# SCH_ProtoDuck_v1_2026-04-04.net
KiCad netlist of a schematic drawn in EasyEDA
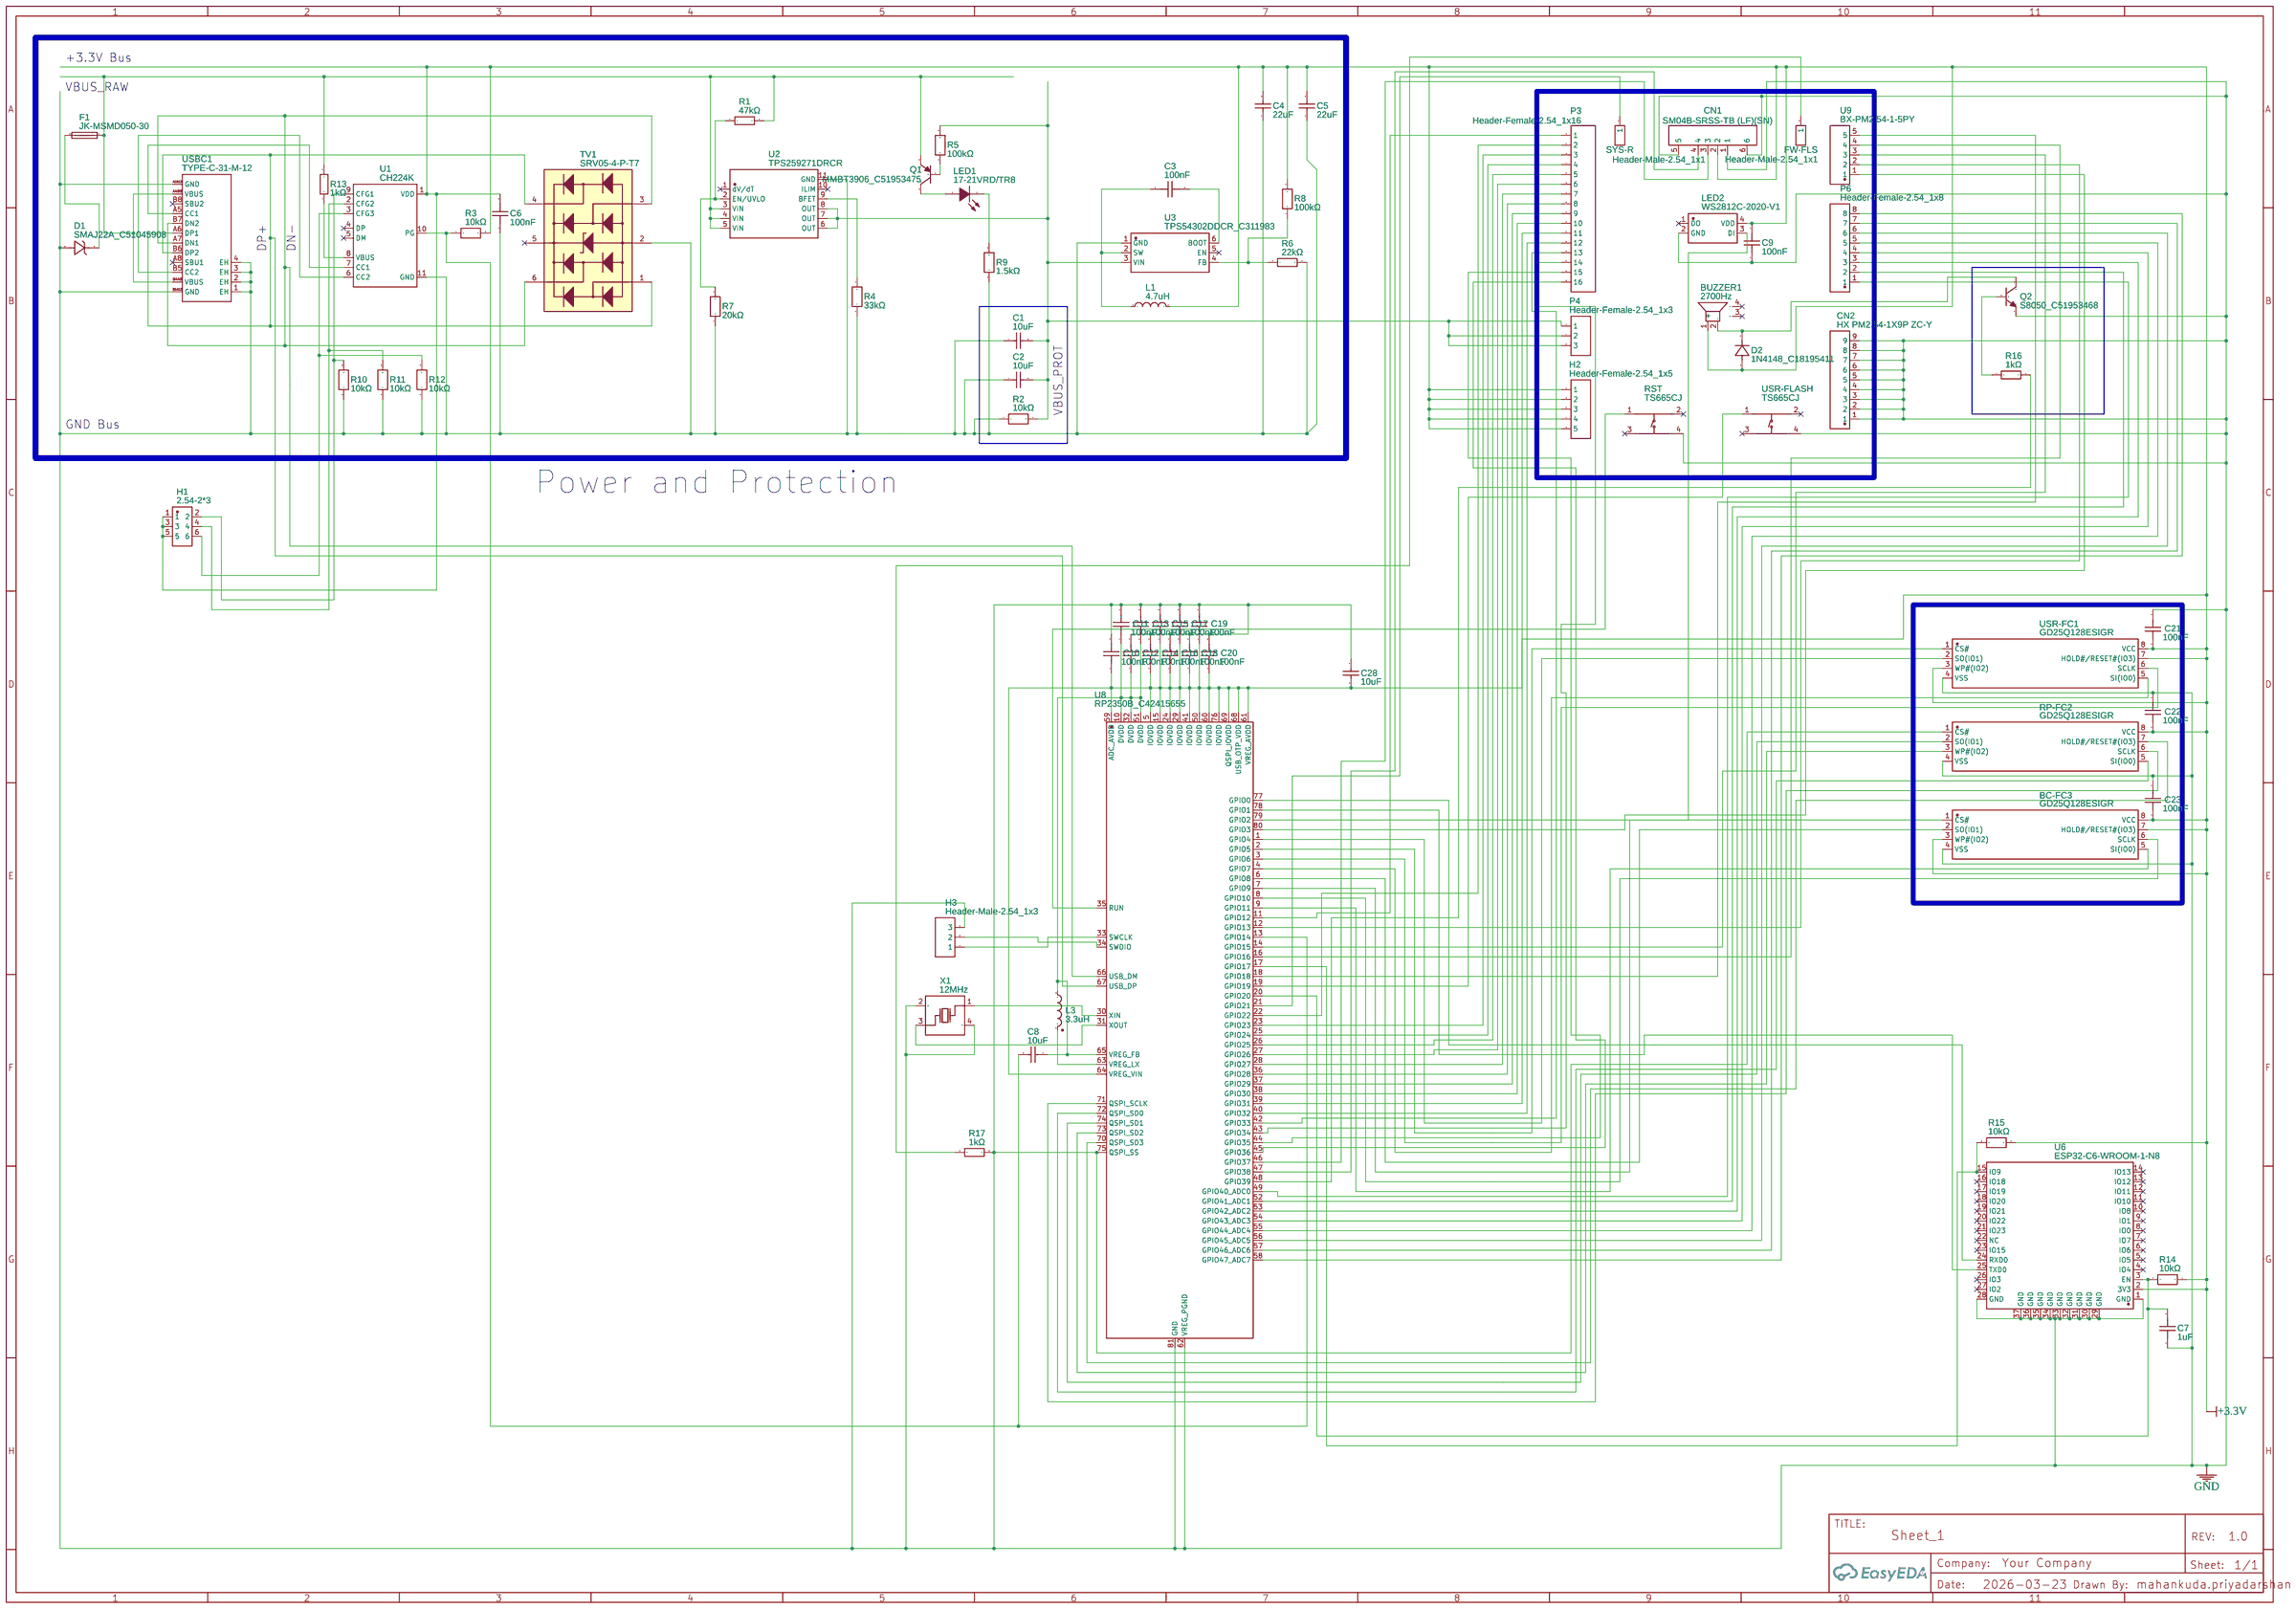
[diagram p0: schematic sheet]

(export (version "E")
  (design (tool "Eeschema 10.0.6"))
  (components
    (comp (ref "BC-FC3")
      (value "GD25Q128ESIGR")
      (fields (field (name "Manufacturer") "GigaDevice(兆易创新)"))
      (libsource (lib "") (part "GD25Q128ESIGR_2"))
    )
    (comp (ref "BUZZER1")
      (value "2700Hz")
      (fields (field (name "Manufacturer Part") "MLT-8540H") (field (name "Manufacturer") "华能"))
      (libsource (lib "") (part "MLT-8540H"))
    )
    (comp (ref "C1")
      (value "10uF")
      (fields
        (field (name "Manufacturer Part") "CL31A106KBHNNNE")
        (field (name "Manufacturer") "SAMSUNG(三星)")
      )
      (libsource (lib "") (part "CL31A106KBHNNNE"))
    )
    (comp (ref "C2")
      (value "10uF")
      (fields
        (field (name "Manufacturer Part") "CL31A106KBHNNNE")
        (field (name "Manufacturer") "SAMSUNG(三星)")
      )
      (libsource (lib "") (part "CL31A106KBHNNNE"))
    )
    (comp (ref "C3")
      (value "100nF")
      (fields
        (field (name "Manufacturer Part") "CC0603KRX7R9BB104")
        (field (name "Manufacturer") "YAGEO(国巨)")
      )
      (libsource (lib "") (part "CC0603KRX7R9BB104"))
    )
    (comp (ref "C4")
      (value "22uF")
      (fields
        (field (name "Manufacturer Part") "CL21A226MOQNNNE")
        (field (name "Manufacturer") "SAMSUNG(三星)")
      )
      (libsource (lib "") (part "CL21A226MOQNNNE"))
    )
    (comp (ref "C5")
      (value "22uF")
      (fields
        (field (name "Manufacturer Part") "CL21A226MOQNNNE")
        (field (name "Manufacturer") "SAMSUNG(三星)")
      )
      (libsource (lib "") (part "CL21A226MOQNNNE"))
    )
    (comp (ref "C6")
      (value "100nF")
      (fields
        (field (name "Manufacturer Part") "CL05B104KB54PNC")
        (field (name "Manufacturer") "SAMSUNG(三星)")
      )
      (libsource (lib "") (part "CL05B104KB54PNC"))
    )
    (comp (ref "C7")
      (value "1uF")
      (fields
        (field (name "Manufacturer Part") "CL10B105KB8NQNC")
        (field (name "Manufacturer") "SAMSUNG(三星)")
      )
      (libsource (lib "") (part "CL10B105KB8NQNC"))
    )
    (comp (ref "C8")
      (value "10uF")
      (fields
        (field (name "Manufacturer Part") "CL31A106KBHNNNE")
        (field (name "Manufacturer") "SAMSUNG(三星)")
      )
      (libsource (lib "") (part "CL31A106KBHNNNE"))
    )
    (comp (ref "C9")
      (value "100nF")
      (fields
        (field (name "Manufacturer Part") "CL05B104KO5NNNC")
        (field (name "Manufacturer") "SAMSUNG(三星)")
      )
      (libsource (lib "") (part "CL05B104KO5NNNC"))
    )
    (comp (ref "C10")
      (value "100nF")
      (fields
        (field (name "Manufacturer Part") "CL05B104KO5NNNC")
        (field (name "Manufacturer") "SAMSUNG(三星)")
      )
      (libsource (lib "") (part "CL05B104KO5NNNC"))
    )
    (comp (ref "C11")
      (value "100nF")
      (fields
        (field (name "Manufacturer Part") "CL05B104KO5NNNC")
        (field (name "Manufacturer") "SAMSUNG(三星)")
      )
      (libsource (lib "") (part "CL05B104KO5NNNC"))
    )
    (comp (ref "C12")
      (value "100nF")
      (fields
        (field (name "Manufacturer Part") "CL05B104KO5NNNC")
        (field (name "Manufacturer") "SAMSUNG(三星)")
      )
      (libsource (lib "") (part "CL05B104KO5NNNC"))
    )
    (comp (ref "C13")
      (value "100nF")
      (fields
        (field (name "Manufacturer Part") "CL05B104KO5NNNC")
        (field (name "Manufacturer") "SAMSUNG(三星)")
      )
      (libsource (lib "") (part "CL05B104KO5NNNC"))
    )
    (comp (ref "C14")
      (value "100nF")
      (fields
        (field (name "Manufacturer Part") "CL05B104KO5NNNC")
        (field (name "Manufacturer") "SAMSUNG(三星)")
      )
      (libsource (lib "") (part "CL05B104KO5NNNC"))
    )
    (comp (ref "C15")
      (value "100nF")
      (fields
        (field (name "Manufacturer Part") "CL05B104KO5NNNC")
        (field (name "Manufacturer") "SAMSUNG(三星)")
      )
      (libsource (lib "") (part "CL05B104KO5NNNC"))
    )
    (comp (ref "C16")
      (value "100nF")
      (fields
        (field (name "Manufacturer Part") "CL05B104KO5NNNC")
        (field (name "Manufacturer") "SAMSUNG(三星)")
      )
      (libsource (lib "") (part "CL05B104KO5NNNC"))
    )
    (comp (ref "C17")
      (value "100nF")
      (fields
        (field (name "Manufacturer Part") "CL05B104KO5NNNC")
        (field (name "Manufacturer") "SAMSUNG(三星)")
      )
      (libsource (lib "") (part "CL05B104KO5NNNC"))
    )
    (comp (ref "C18")
      (value "100nF")
      (fields
        (field (name "Manufacturer Part") "CL05B104KO5NNNC")
        (field (name "Manufacturer") "SAMSUNG(三星)")
      )
      (libsource (lib "") (part "CL05B104KO5NNNC"))
    )
    (comp (ref "C19")
      (value "100nF")
      (fields
        (field (name "Manufacturer Part") "CL05B104KO5NNNC")
        (field (name "Manufacturer") "SAMSUNG(三星)")
      )
      (libsource (lib "") (part "CL05B104KO5NNNC"))
    )
    (comp (ref "C20")
      (value "100nF")
      (fields
        (field (name "Manufacturer Part") "CL05B104KO5NNNC")
        (field (name "Manufacturer") "SAMSUNG(三星)")
      )
      (libsource (lib "") (part "CL05B104KO5NNNC"))
    )
    (comp (ref "C21")
      (value "100nF")
      (fields
        (field (name "Manufacturer Part") "CL05B104KO5NNNC")
        (field (name "Manufacturer") "SAMSUNG(三星)")
      )
      (libsource (lib "") (part "CL05B104KO5NNNC"))
    )
    (comp (ref "C22")
      (value "100nF")
      (fields
        (field (name "Manufacturer Part") "CL05B104KO5NNNC")
        (field (name "Manufacturer") "SAMSUNG(三星)")
      )
      (libsource (lib "") (part "CL05B104KO5NNNC"))
    )
    (comp (ref "C23")
      (value "100nF")
      (fields
        (field (name "Manufacturer Part") "CL05B104KO5NNNC")
        (field (name "Manufacturer") "SAMSUNG(三星)")
      )
      (libsource (lib "") (part "CL05B104KO5NNNC"))
    )
    (comp (ref "C28")
      (value "10uF")
      (fields
        (field (name "Manufacturer Part") "CL05A106MQ5NUNC")
        (field (name "Manufacturer") "SAMSUNG(三星)")
      )
      (libsource (lib "") (part "CL05A106MQ5NUNC"))
    )
    (comp (ref "CN1")
      (value "SM04B-SRSS-TB (LF)(SN)")
      (fields (field (name "Manufacturer Part") "SM04B-SRSS-TB(LF)(SN)") (field (name "Manufacturer") "JST"))
      (libsource (lib "") (part "SM04B-SRSS-TB (LF)(SN)"))
    )
    (comp (ref "CN2")
      (value "HX PM2.54-1X9P ZC-Y")
      (fields
        (field (name "Manufacturer Part") "HX PM2.54-1x9P ZC-Y")
        (field (name "Manufacturer") "hanxia(韩下)")
      )
      (libsource (lib "") (part "HX PM2.54-1X9P ZC-Y"))
    )
    (comp (ref "D1")
      (value "SMAJ22A_C51045908")
      (fields (field (name "Manufacturer Part") "SMAJ22A") (field (name "Manufacturer") "Brightking(君耀电子)"))
      (libsource (lib "") (part "SMAJ22A_C51045908"))
    )
    (comp (ref "D2")
      (value "1N4148_C18195411")
      (fields (field (name "Manufacturer Part") "1N4148") (field (name "Manufacturer") "LJ(朗捷)"))
      (libsource (lib "") (part "1N4148_C18195411"))
    )
    (comp (ref "F1")
      (value "JK-MSMD050-30")
      (fields (field (name "Manufacturer") "JK(金科)"))
      (libsource (lib "") (part "JK-MSMD050-30"))
    )
    (comp (ref "FW-FLS")
      (value "Header-Male-2.54_1x1")
      (fields (field (name "Manufacturer Part") "2.54-1*1P针") (field (name "Manufacturer") "BOOMELE(博穆精密)"))
      (libsource (lib "") (part "Header-Male-2.54_1x1_1"))
    )
    (comp (ref "H1")
      (value "2.54-2*3")
      (fields (field (name "Manufacturer") "ZHOURI(洲日)"))
      (libsource (lib "") (part "2.54-2*3"))
    )
    (comp (ref "H2")
      (value "Header-Female-2.54_1x5")
      (fields (field (name "Manufacturer Part") "2.54-1*5P母") (field (name "Manufacturer") "BOOMELE(博穆精密)"))
      (libsource (lib "") (part "Header-Female-2.54_1x5"))
    )
    (comp (ref "H3")
      (value "Header-Male-2.54_1x3")
      (fields (field (name "Manufacturer Part") "2.54-1*3P针") (field (name "Manufacturer") "BOOMELE(博穆精密)"))
      (libsource (lib "") (part "Header-Male-2.54_1x3"))
    )
    (comp (ref "L1")
      (value "4.7uH")
      (fields
        (field (name "Manufacturer Part") "CKCS6045-4.7uH/M")
        (field (name "Manufacturer") "CENKER(岑科)")
      )
      (libsource (lib "") (part "CKCS6045-4.7UH/M"))
    )
    (comp (ref "L3")
      (value "3.3uH")
      (fields
        (field (name "Manufacturer Part") "AOTA-B201610S3R3-101-T")
        (field (name "Manufacturer") "ABRACON")
      )
      (libsource (lib "") (part "AOTA-B201610S3R3-101-T"))
    )
    (comp (ref "LED1")
      (value "17-21VRD/TR8")
      (fields (field (name "Manufacturer") "EVERLIGHT(亿光)"))
      (libsource (lib "") (part "17-21VRD/TR8"))
    )
    (comp (ref "LED2")
      (value "WS2812C-2020-V1")
      (fields (field (name "Manufacturer") "worldsemi"))
      (libsource (lib "") (part "WS2812C-2020-V1"))
    )
    (comp (ref "P3")
      (value "Header-Female-2.54_1x16")
      (fields (field (name "Manufacturer Part") "2.54-1*16P母") (field (name "Manufacturer") "BOOMELE(博穆精密)"))
      (libsource (lib "") (part "Header-Female-2.54_1x16"))
    )
    (comp (ref "P4")
      (value "Header-Female-2.54_1x3")
      (fields (field (name "Manufacturer Part") "2.54-1*3P母") (field (name "Manufacturer") "BOOMELE(博穆精密)"))
      (libsource (lib "") (part "Header-Female-2.54_1x3"))
    )
    (comp (ref "P6")
      (value "Header-Female-2.54_1x8")
      (fields (field (name "Manufacturer Part") "2.54-1*8P母环保") (field (name "Manufacturer") "BOOMELE(博穆精密)"))
      (libsource (lib "") (part "Header-Female-2.54_1x8"))
    )
    (comp (ref "Q1")
      (value "MMBT3906_C51953475")
      (fields (field (name "Manufacturer Part") "MMBT3906") (field (name "Manufacturer") "CCX(晁禾)"))
      (libsource (lib "") (part "MMBT3906_C51953475"))
    )
    (comp (ref "Q2")
      (value "S8050_C51953468")
      (fields (field (name "Manufacturer Part") "S8050") (field (name "Manufacturer") "CCX(晁禾)"))
      (libsource (lib "") (part "S8050_C51953468"))
    )
    (comp (ref "R1")
      (value "47kΩ")
      (fields
        (field (name "Manufacturer Part") "0603WAF4702T5E")
        (field (name "Manufacturer") "UNI-ROYAL(厚声)")
      )
      (libsource (lib "") (part "0603WAF4702T5E"))
    )
    (comp (ref "R2")
      (value "10kΩ")
      (fields (field (name "Manufacturer Part") "FRC0603J103 TS") (field (name "Manufacturer") "FOJAN(富捷)"))
      (libsource (lib "") (part "FRC0603J103TS"))
    )
    (comp (ref "R3")
      (value "10kΩ")
      (fields (field (name "Manufacturer Part") "FRC0603J103 TS") (field (name "Manufacturer") "FOJAN(富捷)"))
      (libsource (lib "") (part "FRC0603J103TS"))
    )
    (comp (ref "R4")
      (value "33kΩ")
      (fields (field (name "Manufacturer Part") "FRC0603F3302TS") (field (name "Manufacturer") "FOJAN(富捷)"))
      (libsource (lib "") (part "FRC0603F3302TS"))
    )
    (comp (ref "R5")
      (value "100kΩ")
      (fields (field (name "Manufacturer Part") "FRC0603J104 TS") (field (name "Manufacturer") "FOJAN(富捷)"))
      (libsource (lib "") (part "FRC0603J104 TS"))
    )
    (comp (ref "R6")
      (value "22kΩ")
      (fields
        (field (name "Manufacturer Part") "0402WGF2202TCE")
        (field (name "Manufacturer") "UNI-ROYAL(厚声)")
      )
      (libsource (lib "") (part "0402WGF2202TCE"))
    )
    (comp (ref "R7")
      (value "20kΩ")
      (fields (field (name "Manufacturer Part") "FRC0603F2002TS") (field (name "Manufacturer") "FOJAN(富捷)"))
      (libsource (lib "") (part "FRC0603F2002TS"))
    )
    (comp (ref "R8")
      (value "100kΩ")
      (fields (field (name "Manufacturer Part") "FCR0603F100K") (field (name "Manufacturer") "VO(翔胜)"))
      (libsource (lib "") (part "FCR0603F100K"))
    )
    (comp (ref "R9")
      (value "1.5kΩ")
      (fields (field (name "Manufacturer Part") "FRC2512F1501TS") (field (name "Manufacturer") "FOJAN(富捷)"))
      (libsource (lib "") (part "FRC2512F1501TS"))
    )
    (comp (ref "R10")
      (value "10kΩ")
      (fields (field (name "Manufacturer Part") "FRC0603J103 TS") (field (name "Manufacturer") "FOJAN(富捷)"))
      (libsource (lib "") (part "FRC0603J103TS_1"))
    )
    (comp (ref "R11")
      (value "10kΩ")
      (fields (field (name "Manufacturer Part") "FRC0603J103 TS") (field (name "Manufacturer") "FOJAN(富捷)"))
      (libsource (lib "") (part "FRC0603J103TS_1"))
    )
    (comp (ref "R12")
      (value "10kΩ")
      (fields (field (name "Manufacturer Part") "FRC0603J103 TS") (field (name "Manufacturer") "FOJAN(富捷)"))
      (libsource (lib "") (part "FRC0603J103TS_1"))
    )
    (comp (ref "R13")
      (value "1kΩ")
      (fields
        (field (name "Manufacturer Part") "0603WAF1001T5E")
        (field (name "Manufacturer") "UNI-ROYAL(厚声)")
      )
      (libsource (lib "") (part "0603WAF1001T5E"))
    )
    (comp (ref "R14")
      (value "10kΩ")
      (fields (field (name "Manufacturer Part") "FRC0603J103 TS") (field (name "Manufacturer") "FOJAN(富捷)"))
      (libsource (lib "") (part "FRC0603J103TS_2"))
    )
    (comp (ref "R15")
      (value "10kΩ")
      (fields (field (name "Manufacturer Part") "FRC0603J103 TS") (field (name "Manufacturer") "FOJAN(富捷)"))
      (libsource (lib "") (part "FRC0603J103TS_2"))
    )
    (comp (ref "R16")
      (value "1kΩ")
      (fields
        (field (name "Manufacturer Part") "0603WAF1001T5E")
        (field (name "Manufacturer") "UNI-ROYAL(厚声)")
      )
      (libsource (lib "") (part "0603WAF1001T5E_1"))
    )
    (comp (ref "R17")
      (value "1kΩ")
      (fields
        (field (name "Manufacturer Part") "0603WAF1001T5E")
        (field (name "Manufacturer") "UNI-ROYAL(厚声)")
      )
      (libsource (lib "") (part "0603WAF1001T5E_1"))
    )
    (comp (ref "RP-FC2")
      (value "GD25Q128ESIGR")
      (fields (field (name "Manufacturer") "GigaDevice(兆易创新)"))
      (libsource (lib "") (part "GD25Q128ESIGR_1"))
    )
    (comp (ref "RST")
      (value "TS665CJ")
      (fields (field (name "Manufacturer") "SHOU HAN(首韩)"))
      (libsource (lib "") (part "TS665CJ_1"))
    )
    (comp (ref "SYS-R")
      (value "Header-Male-2.54_1x1")
      (fields (field (name "Manufacturer Part") "2.54-1*1P针") (field (name "Manufacturer") "BOOMELE(博穆精密)"))
      (libsource (lib "") (part "Header-Male-2.54_1x1"))
    )
    (comp (ref "TV1")
      (value "SRV05-4-P-T7")
      (fields (field (name "Manufacturer") "PROTEK"))
      (libsource (lib "") (part "SRV05-4-P-T7"))
    )
    (comp (ref "U1")
      (value "CH224K")
      (fields (field (name "Manufacturer") "WCH(南京沁恒)"))
      (libsource (lib "") (part "CH224K"))
    )
    (comp (ref "U2")
      (value "TPS259271DRCR")
      (fields (field (name "Manufacturer") "TI(德州仪器)"))
      (libsource (lib "") (part "TPS259271DRCR"))
    )
    (comp (ref "U3")
      (value "TPS54302DDCR_C311983")
      (fields (field (name "Manufacturer Part") "TPS54302DDCR") (field (name "Manufacturer") "TI(德州仪器)"))
      (libsource (lib "") (part "TPS54302DDCR_C311983"))
    )
    (comp (ref "U6")
      (value "ESP32-C6-WROOM-1-N8")
      (fields (field (name "Manufacturer") "ESPRESSIF(乐鑫)"))
      (libsource (lib "") (part "ESP32-C6-WROOM-1-N8"))
    )
    (comp (ref "U8")
      (value "RP2350B_C42415655")
      (fields (field (name "Manufacturer Part") "RP2350B") (field (name "Manufacturer") "Raspberry Pi(树莓派)"))
      (libsource (lib "") (part "RP2350B_C42415655"))
    )
    (comp (ref "U9")
      (value "BX-PM2.54-1-5PY")
      (fields (field (name "Manufacturer") "Bossie(博锡)"))
      (libsource (lib "") (part "BX-PM2.54-1-5PY"))
    )
    (comp (ref "USBC1")
      (value "TYPE-C-31-M-12")
      (fields (field (name "Manufacturer") "韩国韩荣"))
      (libsource (lib "") (part "TYPE-C-31-M-12"))
    )
    (comp (ref "USR-FC1")
      (value "GD25Q128ESIGR")
      (fields (field (name "Manufacturer") "GigaDevice(兆易创新)"))
      (libsource (lib "") (part "GD25Q128ESIGR"))
    )
    (comp (ref "USR-FLASH")
      (value "TS665CJ")
      (fields (field (name "Manufacturer") "SHOU HAN(首韩)"))
      (libsource (lib "") (part "TS665CJ"))
    )
    (comp (ref "X1")
      (value "12MHz")
      (fields (field (name "Manufacturer Part") "X322512MSB4SI") (field (name "Manufacturer") "YXC(扬兴晶振)"))
      (libsource (lib "") (part "X322512MSB4SI"))
    )
  )
  (nets
    (net (code "1") (name "+3.3V") (class "Default")
      (node (ref "BC-FC3") (pin "3") (pinfunction "WP#(IO2)_3") (pintype "unspecified"))
      (node (ref "BC-FC3") (pin "7") (pinfunction "HOLD#/RESET#(IO3)_7") (pintype "unspecified"))
      (node (ref "BC-FC3") (pin "8") (pinfunction "VCC_8") (pintype "unspecified"))
      (node (ref "BUZZER1") (pin "1") (pinfunction "+_1") (pintype "unspecified"))
      (node (ref "C10") (pin "1") (pinfunction "1_1") (pintype "unspecified"))
      (node (ref "C14") (pin "1") (pinfunction "1_1") (pintype "unspecified"))
      (node (ref "C15") (pin "1") (pinfunction "1_1") (pintype "unspecified"))
      (node (ref "C16") (pin "1") (pinfunction "1_1") (pintype "unspecified"))
      (node (ref "C17") (pin "1") (pinfunction "1_1") (pintype "unspecified"))
      (node (ref "C18") (pin "1") (pinfunction "1_1") (pintype "unspecified"))
      (node (ref "C19") (pin "1") (pinfunction "1_1") (pintype "unspecified"))
      (node (ref "C20") (pin "1") (pinfunction "1_1") (pintype "unspecified"))
      (node (ref "C21") (pin "1") (pinfunction "1_1") (pintype "unspecified"))
      (node (ref "C22") (pin "1") (pinfunction "1_1") (pintype "unspecified"))
      (node (ref "C23") (pin "1") (pinfunction "1_1") (pintype "unspecified"))
      (node (ref "C28") (pin "1") (pinfunction "1_1") (pintype "input"))
      (node (ref "C4") (pin "2") (pinfunction "2_2") (pintype "input"))
      (node (ref "C5") (pin "2") (pinfunction "2_2") (pintype "input"))
      (node (ref "C6") (pin "2") (pinfunction "2_2") (pintype "unspecified"))
      (node (ref "C9") (pin "2") (pinfunction "2_2") (pintype "unspecified"))
      (node (ref "CN1") (pin "2") (pinfunction "2_2") (pintype "unspecified"))
      (node (ref "D2") (pin "1") (pinfunction "A_1") (pintype "unspecified"))
      (node (ref "H1") (pin "1") (pinfunction "1_1") (pintype "unspecified"))
      (node (ref "H1") (pin "3") (pinfunction "3_3") (pintype "unspecified"))
      (node (ref "H1") (pin "5") (pinfunction "5_5") (pintype "unspecified"))
      (node (ref "H2") (pin "1") (pinfunction "1_1") (pintype "input"))
      (node (ref "H2") (pin "2") (pinfunction "2_2") (pintype "input"))
      (node (ref "H2") (pin "3") (pinfunction "3_3") (pintype "input"))
      (node (ref "H2") (pin "4") (pinfunction "4_4") (pintype "input"))
      (node (ref "H2") (pin "5") (pinfunction "5_5") (pintype "input"))
      (node (ref "L1") (pin "2") (pinfunction "2_2") (pintype "unspecified"))
      (node (ref "LED2") (pin "4") (pinfunction "VDD_4") (pintype "unspecified"))
      (node (ref "R14") (pin "1") (pinfunction "1_1") (pintype "unspecified"))
      (node (ref "R15") (pin "1") (pinfunction "1_1") (pintype "unspecified"))
      (node (ref "R3") (pin "2") (pinfunction "2_2") (pintype "unspecified"))
      (node (ref "R8") (pin "2") (pinfunction "2_2") (pintype "unspecified"))
      (node (ref "RP-FC2") (pin "8") (pinfunction "VCC_8") (pintype "unspecified"))
      (node (ref "U1") (pin "1") (pinfunction "VDD_1") (pintype "unspecified"))
      (node (ref "U6") (pin "2") (pinfunction "3V3_2") (pintype "unspecified"))
      (node (ref "U8") (pin "15") (pinfunction "IOVDD_15") (pintype "unspecified"))
      (node (ref "U8") (pin "24") (pinfunction "IOVDD_24") (pintype "unspecified"))
      (node (ref "U8") (pin "29") (pinfunction "IOVDD_29") (pintype "unspecified"))
      (node (ref "U8") (pin "41") (pinfunction "IOVDD_41") (pintype "unspecified"))
      (node (ref "U8") (pin "5") (pinfunction "IOVDD_5") (pintype "unspecified"))
      (node (ref "U8") (pin "50") (pinfunction "IOVDD_50") (pintype "unspecified"))
      (node (ref "U8") (pin "59") (pinfunction "ADC_AVDD_59") (pintype "unspecified"))
      (node (ref "U8") (pin "60") (pinfunction "IOVDD_60") (pintype "unspecified"))
      (node (ref "U8") (pin "61") (pinfunction "VREG_AVDD_61") (pintype "unspecified"))
      (node (ref "U8") (pin "64") (pinfunction "VREG_VIN_64") (pintype "unspecified"))
      (node (ref "U8") (pin "68") (pinfunction "USB_OTP_VDD_68") (pintype "unspecified"))
      (node (ref "U8") (pin "69") (pinfunction "QSPI_IOVDD_69") (pintype "unspecified"))
      (node (ref "U8") (pin "76") (pinfunction "IOVDD_76") (pintype "unspecified"))
      (node (ref "USR-FC1") (pin "3") (pinfunction "WP#(IO2)_3") (pintype "unspecified"))
      (node (ref "USR-FC1") (pin "7") (pinfunction "HOLD#/RESET#(IO3)_7") (pintype "unspecified"))
      (node (ref "USR-FC1") (pin "8") (pinfunction "VCC_8") (pintype "unspecified"))
    )
    (net (code "2") (name "GND") (class "Default")
      (node (ref "BC-FC3") (pin "4") (pinfunction "VSS_4") (pintype "unspecified"))
      (node (ref "C1") (pin "1") (pinfunction "1_1") (pintype "input"))
      (node (ref "C10") (pin "2") (pinfunction "2_2") (pintype "unspecified"))
      (node (ref "C11") (pin "2") (pinfunction "2_2") (pintype "unspecified"))
      (node (ref "C12") (pin "2") (pinfunction "2_2") (pintype "unspecified"))
      (node (ref "C13") (pin "2") (pinfunction "2_2") (pintype "unspecified"))
      (node (ref "C14") (pin "2") (pinfunction "2_2") (pintype "unspecified"))
      (node (ref "C15") (pin "2") (pinfunction "2_2") (pintype "unspecified"))
      (node (ref "C16") (pin "2") (pinfunction "2_2") (pintype "unspecified"))
      (node (ref "C17") (pin "2") (pinfunction "2_2") (pintype "unspecified"))
      (node (ref "C18") (pin "2") (pinfunction "2_2") (pintype "unspecified"))
      (node (ref "C19") (pin "2") (pinfunction "2_2") (pintype "unspecified"))
      (node (ref "C2") (pin "1") (pinfunction "1_1") (pintype "input"))
      (node (ref "C20") (pin "2") (pinfunction "2_2") (pintype "unspecified"))
      (node (ref "C21") (pin "2") (pinfunction "2_2") (pintype "unspecified"))
      (node (ref "C22") (pin "2") (pinfunction "2_2") (pintype "unspecified"))
      (node (ref "C23") (pin "2") (pinfunction "2_2") (pintype "unspecified"))
      (node (ref "C28") (pin "2") (pinfunction "2_2") (pintype "input"))
      (node (ref "C4") (pin "1") (pinfunction "1_1") (pintype "input"))
      (node (ref "C5") (pin "1") (pinfunction "1_1") (pintype "input"))
      (node (ref "C6") (pin "1") (pinfunction "1_1") (pintype "unspecified"))
      (node (ref "C7") (pin "2") (pinfunction "2_2") (pintype "unspecified"))
      (node (ref "C9") (pin "1") (pinfunction "1_1") (pintype "unspecified"))
      (node (ref "CN1") (pin "1") (pinfunction "1_1") (pintype "unspecified"))
      (node (ref "CN1") (pin "5") (pinfunction "5_5") (pintype "unspecified"))
      (node (ref "CN1") (pin "6") (pinfunction "6_6") (pintype "unspecified"))
      (node (ref "CN2") (pin "1") (pinfunction "1_1") (pintype "unspecified"))
      (node (ref "CN2") (pin "2") (pinfunction "2_2") (pintype "unspecified"))
      (node (ref "CN2") (pin "3") (pinfunction "3_3") (pintype "unspecified"))
      (node (ref "CN2") (pin "4") (pinfunction "4_4") (pintype "unspecified"))
      (node (ref "CN2") (pin "5") (pinfunction "5_5") (pintype "unspecified"))
      (node (ref "CN2") (pin "6") (pinfunction "6_6") (pintype "unspecified"))
      (node (ref "CN2") (pin "7") (pinfunction "7_7") (pintype "unspecified"))
      (node (ref "CN2") (pin "8") (pinfunction "8_8") (pintype "unspecified"))
      (node (ref "CN2") (pin "9") (pinfunction "9_9") (pintype "unspecified"))
      (node (ref "D1") (pin "2") (pinfunction "A_2") (pintype "unspecified"))
      (node (ref "H3") (pin "3") (pinfunction "3_3") (pintype "input"))
      (node (ref "LED2") (pin "2") (pinfunction "GND_2") (pintype "unspecified"))
      (node (ref "Q2") (pin "2") (pinfunction "E_2") (pintype "unspecified"))
      (node (ref "R10") (pin "1") (pinfunction "1_1") (pintype "unspecified"))
      (node (ref "R11") (pin "1") (pinfunction "1_1") (pintype "unspecified"))
      (node (ref "R12") (pin "1") (pinfunction "1_1") (pintype "unspecified"))
      (node (ref "R17") (pin "2") (pinfunction "2_2") (pintype "input"))
      (node (ref "R2") (pin "1") (pinfunction "1_1") (pintype "unspecified"))
      (node (ref "R4") (pin "1") (pinfunction "1_1") (pintype "unspecified"))
      (node (ref "R6") (pin "2") (pinfunction "2_2") (pintype "input"))
      (node (ref "R7") (pin "1") (pinfunction "1_1") (pintype "unspecified"))
      (node (ref "R9") (pin "1") (pinfunction "1_1") (pintype "unspecified"))
      (node (ref "RP-FC2") (pin "1") (pinfunction "CS#_1") (pintype "unspecified"))
      (node (ref "RP-FC2") (pin "4") (pinfunction "VSS_4") (pintype "unspecified"))
      (node (ref "RST") (pin "4") (pinfunction "D_4") (pintype "unspecified"))
      (node (ref "TV1") (pin "2") (pinfunction "2_2") (pintype "input"))
      (node (ref "U1") (pin "11") (pinfunction "GND_11") (pintype "unspecified"))
      (node (ref "U2") (pin "11") (pinfunction "GND_11") (pintype "unspecified"))
      (node (ref "U3") (pin "1") (pinfunction "GND_1") (pintype "unspecified"))
      (node (ref "U6") (pin "1") (pinfunction "GND_1") (pintype "unspecified"))
      (node (ref "U6") (pin "28") (pinfunction "GND_28") (pintype "unspecified"))
      (node (ref "U6") (pin "29") (pinfunction "GND_29") (pintype "unspecified"))
      (node (ref "U6") (pin "30") (pinfunction "GND_30") (pintype "unspecified"))
      (node (ref "U6") (pin "31") (pinfunction "GND_31") (pintype "unspecified"))
      (node (ref "U6") (pin "32") (pinfunction "GND_32") (pintype "unspecified"))
      (node (ref "U6") (pin "33") (pinfunction "GND_33") (pintype "unspecified"))
      (node (ref "U6") (pin "34") (pinfunction "GND_34") (pintype "unspecified"))
      (node (ref "U6") (pin "35") (pinfunction "GND_35") (pintype "unspecified"))
      (node (ref "U6") (pin "36") (pinfunction "GND_36") (pintype "unspecified"))
      (node (ref "U6") (pin "37") (pinfunction "GND_37") (pintype "unspecified"))
      (node (ref "U8") (pin "62") (pinfunction "VREG_PGND_62") (pintype "unspecified"))
      (node (ref "U8") (pin "75") (pinfunction "QSPI_SS_75") (pintype "unspecified"))
      (node (ref "U8") (pin "81") (pinfunction "GND_81") (pintype "unspecified"))
      (node (ref "USBC1") (pin "1") (pinfunction "EH_1") (pintype "unspecified"))
      (node (ref "USBC1") (pin "2") (pinfunction "EH_2") (pintype "unspecified"))
      (node (ref "USBC1") (pin "3") (pinfunction "EH_3") (pintype "unspecified"))
      (node (ref "USBC1") (pin "4") (pinfunction "EH_4") (pintype "unspecified"))
      (node (ref "USBC1") (pin "A1B12") (pinfunction "GND_A1B12") (pintype "unspecified"))
      (node (ref "USBC1") (pin "B1A12") (pinfunction "GND_B1A12") (pintype "unspecified"))
      (node (ref "USR-FC1") (pin "4") (pinfunction "VSS_4") (pintype "unspecified"))
      (node (ref "USR-FLASH") (pin "4") (pinfunction "D_4") (pintype "unspecified"))
      (node (ref "X1") (pin "2") (pinfunction "GND_2") (pintype "unspecified"))
      (node (ref "X1") (pin "4") (pinfunction "GND_4") (pintype "unspecified"))
    )
    (net (code "3") (name "Net-(BC-FC3-CS#)") (class "Default")
      (node (ref "BC-FC3") (pin "1") (pinfunction "CS#_1") (pintype "unspecified"))
      (node (ref "U8") (pin "7") (pinfunction "GPIO9_7") (pintype "unspecified"))
    )
    (net (code "4") (name "Net-(BC-FC3-SCLK)") (class "Default")
      (node (ref "BC-FC3") (pin "6") (pinfunction "SCLK_6") (pintype "unspecified"))
      (node (ref "U8") (pin "8") (pinfunction "GPIO10_8") (pintype "unspecified"))
    )
    (net (code "5") (name "Net-(BC-FC3-SI(IO0))") (class "Default")
      (node (ref "BC-FC3") (pin "5") (pinfunction "SI(IO0)_5") (pintype "unspecified"))
      (node (ref "U8") (pin "9") (pinfunction "GPIO11_9") (pintype "unspecified"))
    )
    (net (code "6") (name "Net-(BC-FC3-SO(IO1))") (class "Default")
      (node (ref "BC-FC3") (pin "2") (pinfunction "SO(IO1)_2") (pintype "unspecified"))
      (node (ref "U8") (pin "6") (pinfunction "GPIO8_6") (pintype "unspecified"))
    )
    (net (code "7") (name "Net-(D1-K)") (class "Default")
      (node (ref "D1") (pin "1") (pinfunction "K_1") (pintype "unspecified"))
      (node (ref "F1") (pin "2") (pinfunction "2_2") (pintype "unspecified"))
    )
    (net (code "8") (name "Net-(D2-C)") (class "Default")
      (node (ref "BUZZER1") (pin "2") (pinfunction "2_2") (pintype "unspecified"))
      (node (ref "D2") (pin "2") (pinfunction "C_2") (pintype "unspecified"))
      (node (ref "Q2") (pin "3") (pinfunction "C_3") (pintype "unspecified"))
    )
    (net (code "9") (name "Net-(FW-FLS-Pad1)") (class "Default")
      (node (ref "FW-FLS") (pin "1") (pinfunction "1_1") (pintype "input"))
      (node (ref "R17") (pin "1") (pinfunction "1_1") (pintype "input"))
    )
    (net (code "10") (name "Net-(LED1-A)") (class "Default")
      (node (ref "LED1") (pin "1") (pinfunction "A_1") (pintype "unspecified"))
      (node (ref "Q1") (pin "3") (pinfunction "C_3") (pintype "unspecified"))
    )
    (net (code "11") (name "Net-(LED1-K)") (class "Default")
      (node (ref "LED1") (pin "2") (pinfunction "K_2") (pintype "unspecified"))
      (node (ref "R9") (pin "2") (pinfunction "2_2") (pintype "unspecified"))
    )
    (net (code "12") (name "Net-(LED2-DI)") (class "Default")
      (node (ref "LED2") (pin "3") (pinfunction "DI_3") (pintype "unspecified"))
      (node (ref "U8") (pin "79") (pinfunction "GPIO2_79") (pintype "unspecified"))
    )
    (net (code "13") (name "Net-(Q1-B)") (class "Default")
      (node (ref "Q1") (pin "1") (pinfunction "B_1") (pintype "unspecified"))
      (node (ref "R5") (pin "1") (pinfunction "1_1") (pintype "unspecified"))
    )
    (net (code "14") (name "Net-(Q1-E)") (class "Default")
      (node (ref "F1") (pin "1") (pinfunction "1_1") (pintype "unspecified"))
      (node (ref "Q1") (pin "2") (pinfunction "E_2") (pintype "unspecified"))
      (node (ref "R1") (pin "2") (pinfunction "2_2") (pintype "input"))
      (node (ref "R13") (pin "2") (pinfunction "2_2") (pintype "input"))
      (node (ref "U2") (pin "3") (pinfunction "VIN_3") (pintype "unspecified"))
      (node (ref "U2") (pin "4") (pinfunction "VIN_4") (pintype "unspecified"))
      (node (ref "U2") (pin "5") (pinfunction "VIN_5") (pintype "unspecified"))
      (node (ref "USBC1") (pin "A4B9") (pinfunction "VBUS_A4B9") (pintype "unspecified"))
      (node (ref "USBC1") (pin "B4A9") (pinfunction "VBUS_B4A9") (pintype "unspecified"))
    )
    (net (code "15") (name "Net-(Q2-B)") (class "Default")
      (node (ref "Q2") (pin "1") (pinfunction "B_1") (pintype "unspecified"))
      (node (ref "R16") (pin "1") (pinfunction "1_1") (pintype "input"))
    )
    (net (code "16") (name "Net-(RP-FC2-HOLD#{slash}RESET#(IO3))") (class "Default")
      (node (ref "RP-FC2") (pin "7") (pinfunction "HOLD#/RESET#(IO3)_7") (pintype "unspecified"))
      (node (ref "U8") (pin "70") (pinfunction "QSPI_SD3_70") (pintype "unspecified"))
    )
    (net (code "17") (name "Net-(RP-FC2-SCLK)") (class "Default")
      (node (ref "RP-FC2") (pin "6") (pinfunction "SCLK_6") (pintype "unspecified"))
      (node (ref "U8") (pin "71") (pinfunction "QSPI_SCLK_71") (pintype "unspecified"))
    )
    (net (code "18") (name "Net-(RP-FC2-SI(IO0))") (class "Default")
      (node (ref "RP-FC2") (pin "5") (pinfunction "SI(IO0)_5") (pintype "unspecified"))
      (node (ref "U8") (pin "72") (pinfunction "QSPI_SD0_72") (pintype "unspecified"))
    )
    (net (code "19") (name "Net-(RP-FC2-SO(IO1))") (class "Default")
      (node (ref "RP-FC2") (pin "2") (pinfunction "SO(IO1)_2") (pintype "unspecified"))
      (node (ref "U8") (pin "74") (pinfunction "QSPI_SD1_74") (pintype "unspecified"))
    )
    (net (code "20") (name "Net-(RP-FC2-WP#(IO2))") (class "Default")
      (node (ref "RP-FC2") (pin "3") (pinfunction "WP#(IO2)_3") (pintype "unspecified"))
      (node (ref "U8") (pin "73") (pinfunction "QSPI_SD2_73") (pintype "unspecified"))
    )
    (net (code "21") (name "Net-(RST-A)") (class "Default")
      (node (ref "RST") (pin "1") (pinfunction "A_1") (pintype "unspecified"))
      (node (ref "U8") (pin "35") (pinfunction "RUN_35") (pintype "unspecified"))
    )
    (net (code "22") (name "Net-(U1-CC1)") (class "Default")
      (node (ref "U1") (pin "7") (pinfunction "CC1_7") (pintype "unspecified"))
      (node (ref "USBC1") (pin "A5") (pinfunction "CC1_A5") (pintype "unspecified"))
    )
    (net (code "23") (name "Net-(U1-CC2)") (class "Default")
      (node (ref "U1") (pin "6") (pinfunction "CC2_6") (pintype "unspecified"))
      (node (ref "USBC1") (pin "B5") (pinfunction "CC2_B5") (pintype "unspecified"))
    )
    (net (code "24") (name "Net-(U1-CFG1)") (class "Default")
      (node (ref "H1") (pin "2") (pinfunction "2_2") (pintype "unspecified"))
      (node (ref "R10") (pin "2") (pinfunction "2_2") (pintype "unspecified"))
      (node (ref "U1") (pin "9") (pinfunction "CFG1_9") (pintype "unspecified"))
    )
    (net (code "25") (name "Net-(U1-CFG2)") (class "Default")
      (node (ref "H1") (pin "4") (pinfunction "4_4") (pintype "unspecified"))
      (node (ref "R11") (pin "2") (pinfunction "2_2") (pintype "unspecified"))
      (node (ref "U1") (pin "2") (pinfunction "CFG2_2") (pintype "unspecified"))
    )
    (net (code "26") (name "Net-(U1-CFG3)") (class "Default")
      (node (ref "H1") (pin "6") (pinfunction "6_6") (pintype "unspecified"))
      (node (ref "R12") (pin "2") (pinfunction "2_2") (pintype "unspecified"))
      (node (ref "U1") (pin "3") (pinfunction "CFG3_3") (pintype "unspecified"))
    )
    (net (code "27") (name "Net-(U1-PG)") (class "Default")
      (node (ref "C8") (pin "1") (pinfunction "1_1") (pintype "input"))
      (node (ref "R3") (pin "1") (pinfunction "1_1") (pintype "unspecified"))
      (node (ref "U1") (pin "10") (pinfunction "PG_10") (pintype "unspecified"))
      (node (ref "U8") (pin "13") (pinfunction "GPIO14_13") (pintype "unspecified"))
    )
    (net (code "28") (name "Net-(U1-VBUS)") (class "Default")
      (node (ref "R13") (pin "1") (pinfunction "1_1") (pintype "input"))
      (node (ref "U1") (pin "8") (pinfunction "VBUS_8") (pintype "unspecified"))
    )
    (net (code "29") (name "Net-(U2-BFET)") (class "Default")
      (node (ref "R4") (pin "2") (pinfunction "2_2") (pintype "unspecified"))
      (node (ref "U2") (pin "9") (pinfunction "BFET_9") (pintype "unspecified"))
    )
    (net (code "30") (name "Net-(U2-EN{slash}UVLO)") (class "Default")
      (node (ref "R1") (pin "1") (pinfunction "1_1") (pintype "input"))
      (node (ref "R7") (pin "2") (pinfunction "2_2") (pintype "unspecified"))
      (node (ref "U2") (pin "2") (pinfunction "EN/UVLO_2") (pintype "unspecified"))
    )
    (net (code "31") (name "Net-(U3-BOOT)") (class "Default")
      (node (ref "C3") (pin "2") (pinfunction "2_2") (pintype "unspecified"))
      (node (ref "U3") (pin "6") (pinfunction "BOOT_6") (pintype "unspecified"))
    )
    (net (code "32") (name "Net-(U3-FB)") (class "Default")
      (node (ref "R6") (pin "1") (pinfunction "1_1") (pintype "input"))
      (node (ref "R8") (pin "1") (pinfunction "1_1") (pintype "unspecified"))
      (node (ref "U3") (pin "4") (pinfunction "FB_4") (pintype "unspecified"))
    )
    (net (code "33") (name "Net-(U3-SW)") (class "Default")
      (node (ref "C3") (pin "1") (pinfunction "1_1") (pintype "unspecified"))
      (node (ref "L1") (pin "1") (pinfunction "1_1") (pintype "unspecified"))
      (node (ref "U3") (pin "2") (pinfunction "SW_2") (pintype "unspecified"))
    )
    (net (code "34") (name "Net-(U3-VIN)") (class "Default")
      (node (ref "C1") (pin "2") (pinfunction "2_2") (pintype "input"))
      (node (ref "C2") (pin "2") (pinfunction "2_2") (pintype "input"))
      (node (ref "P4") (pin "1") (pinfunction "1_1") (pintype "input"))
      (node (ref "P4") (pin "2") (pinfunction "2_2") (pintype "input"))
      (node (ref "P4") (pin "3") (pinfunction "3_3") (pintype "input"))
      (node (ref "R2") (pin "2") (pinfunction "2_2") (pintype "unspecified"))
      (node (ref "R5") (pin "2") (pinfunction "2_2") (pintype "unspecified"))
      (node (ref "U2") (pin "6") (pinfunction "OUT_6") (pintype "unspecified"))
      (node (ref "U2") (pin "7") (pinfunction "OUT_7") (pintype "unspecified"))
      (node (ref "U2") (pin "8") (pinfunction "OUT_8") (pintype "unspecified"))
      (node (ref "U3") (pin "3") (pinfunction "VIN_3") (pintype "unspecified"))
    )
    (net (code "35") (name "Net-(U6-EN)") (class "Default")
      (node (ref "C7") (pin "1") (pinfunction "1_1") (pintype "unspecified"))
      (node (ref "R14") (pin "2") (pinfunction "2_2") (pintype "unspecified"))
      (node (ref "U6") (pin "3") (pinfunction "EN_3") (pintype "unspecified"))
      (node (ref "U8") (pin "20") (pinfunction "GPIO20_20") (pintype "unspecified"))
    )
    (net (code "36") (name "Net-(U6-IO9)") (class "Default")
      (node (ref "R15") (pin "2") (pinfunction "2_2") (pintype "unspecified"))
      (node (ref "U6") (pin "15") (pinfunction "IO9_15") (pintype "unspecified"))
      (node (ref "U8") (pin "17") (pinfunction "GPIO17_17") (pintype "unspecified"))
    )
    (net (code "37") (name "Net-(U6-RXD0)") (class "Default")
      (node (ref "U6") (pin "24") (pinfunction "RXD0_24") (pintype "unspecified"))
      (node (ref "U8") (pin "77") (pinfunction "GPIO0_77") (pintype "unspecified"))
    )
    (net (code "38") (name "Net-(U6-TXD0)") (class "Default")
      (node (ref "U6") (pin "25") (pinfunction "TXD0_25") (pintype "unspecified"))
      (node (ref "U8") (pin "78") (pinfunction "GPIO1_78") (pintype "unspecified"))
    )
    (net (code "39") (name "Net-(U8-GPIO3)") (class "Default")
      (node (ref "U8") (pin "80") (pinfunction "GPIO3_80") (pintype "unspecified"))
      (node (ref "U9") (pin "1") (pinfunction "1_1") (pintype "unspecified"))
    )
    (net (code "40") (name "Net-(U8-GPIO4)") (class "Default")
      (node (ref "U8") (pin "1") (pinfunction "GPIO4_1") (pintype "unspecified"))
      (node (ref "USR-FC1") (pin "2") (pinfunction "SO(IO1)_2") (pintype "unspecified"))
    )
    (net (code "41") (name "Net-(U8-GPIO5)") (class "Default")
      (node (ref "U8") (pin "2") (pinfunction "GPIO5_2") (pintype "unspecified"))
      (node (ref "USR-FC1") (pin "1") (pinfunction "CS#_1") (pintype "unspecified"))
    )
    (net (code "42") (name "Net-(U8-GPIO6)") (class "Default")
      (node (ref "U8") (pin "3") (pinfunction "GPIO6_3") (pintype "unspecified"))
      (node (ref "USR-FC1") (pin "6") (pinfunction "SCLK_6") (pintype "unspecified"))
    )
    (net (code "43") (name "Net-(U8-GPIO7)") (class "Default")
      (node (ref "U8") (pin "4") (pinfunction "GPIO7_4") (pintype "unspecified"))
      (node (ref "USR-FC1") (pin "5") (pinfunction "SI(IO0)_5") (pintype "unspecified"))
    )
    (net (code "44") (name "Net-(U8-GPIO12)") (class "Default")
      (node (ref "P3") (pin "1") (pinfunction "1_1") (pintype "input"))
      (node (ref "U8") (pin "11") (pinfunction "GPIO12_11") (pintype "unspecified"))
    )
    (net (code "45") (name "Net-(U8-GPIO13)") (class "Default")
      (node (ref "U8") (pin "12") (pinfunction "GPIO13_12") (pintype "unspecified"))
      (node (ref "U9") (pin "2") (pinfunction "2_2") (pintype "unspecified"))
    )
    (net (code "46") (name "Net-(U8-GPIO15)") (class "Default")
      (node (ref "U8") (pin "14") (pinfunction "GPIO15_14") (pintype "unspecified"))
      (node (ref "U9") (pin "3") (pinfunction "3_3") (pintype "unspecified"))
    )
    (net (code "47") (name "Net-(U8-GPIO16)") (class "Default")
      (node (ref "U8") (pin "16") (pinfunction "GPIO16_16") (pintype "unspecified"))
      (node (ref "U9") (pin "4") (pinfunction "4_4") (pintype "unspecified"))
    )
    (net (code "48") (name "Net-(U8-GPIO18)") (class "Default")
      (node (ref "U8") (pin "18") (pinfunction "GPIO18_18") (pintype "unspecified"))
      (node (ref "U9") (pin "5") (pinfunction "5_5") (pintype "unspecified"))
    )
    (net (code "49") (name "Net-(U8-GPIO19)") (class "Default")
      (node (ref "U8") (pin "19") (pinfunction "GPIO19_19") (pintype "unspecified"))
      (node (ref "USR-FLASH") (pin "1") (pinfunction "A_1") (pintype "unspecified"))
    )
    (net (code "50") (name "Net-(U8-GPIO21)") (class "Default")
      (node (ref "SYS-R") (pin "1") (pinfunction "1_1") (pintype "input"))
      (node (ref "U8") (pin "21") (pinfunction "GPIO21_21") (pintype "unspecified"))
    )
    (net (code "51") (name "Net-(U8-GPIO22)") (class "Default")
      (node (ref "P3") (pin "2") (pinfunction "2_2") (pintype "input"))
      (node (ref "U8") (pin "22") (pinfunction "GPIO22_22") (pintype "unspecified"))
    )
    (net (code "52") (name "Net-(U8-GPIO23)") (class "Default")
      (node (ref "P3") (pin "3") (pinfunction "3_3") (pintype "input"))
      (node (ref "U8") (pin "23") (pinfunction "GPIO23_23") (pintype "unspecified"))
    )
    (net (code "53") (name "Net-(U8-GPIO24)") (class "Default")
      (node (ref "P3") (pin "4") (pinfunction "4_4") (pintype "input"))
      (node (ref "U8") (pin "25") (pinfunction "GPIO24_25") (pintype "unspecified"))
    )
    (net (code "54") (name "Net-(U8-GPIO25)") (class "Default")
      (node (ref "P3") (pin "5") (pinfunction "5_5") (pintype "input"))
      (node (ref "U8") (pin "26") (pinfunction "GPIO25_26") (pintype "unspecified"))
    )
    (net (code "55") (name "Net-(U8-GPIO26)") (class "Default")
      (node (ref "P3") (pin "6") (pinfunction "6_6") (pintype "input"))
      (node (ref "U8") (pin "27") (pinfunction "GPIO26_27") (pintype "unspecified"))
    )
    (net (code "56") (name "Net-(U8-GPIO27)") (class "Default")
      (node (ref "P3") (pin "7") (pinfunction "7_7") (pintype "input"))
      (node (ref "U8") (pin "28") (pinfunction "GPIO27_28") (pintype "unspecified"))
    )
    (net (code "57") (name "Net-(U8-GPIO28)") (class "Default")
      (node (ref "P3") (pin "8") (pinfunction "8_8") (pintype "input"))
      (node (ref "U8") (pin "36") (pinfunction "GPIO28_36") (pintype "unspecified"))
    )
    (net (code "58") (name "Net-(U8-GPIO29)") (class "Default")
      (node (ref "P3") (pin "9") (pinfunction "9_9") (pintype "input"))
      (node (ref "U8") (pin "37") (pinfunction "GPIO29_37") (pintype "unspecified"))
    )
    (net (code "59") (name "Net-(U8-GPIO30)") (class "Default")
      (node (ref "P3") (pin "10") (pinfunction "10_10") (pintype "input"))
      (node (ref "U8") (pin "38") (pinfunction "GPIO30_38") (pintype "unspecified"))
    )
    (net (code "60") (name "Net-(U8-GPIO31)") (class "Default")
      (node (ref "P3") (pin "11") (pinfunction "11_11") (pintype "input"))
      (node (ref "U8") (pin "39") (pinfunction "GPIO31_39") (pintype "unspecified"))
    )
    (net (code "61") (name "Net-(U8-GPIO32)") (class "Default")
      (node (ref "P3") (pin "12") (pinfunction "12_12") (pintype "input"))
      (node (ref "U8") (pin "40") (pinfunction "GPIO32_40") (pintype "unspecified"))
    )
    (net (code "62") (name "Net-(U8-GPIO33)") (class "Default")
      (node (ref "P3") (pin "13") (pinfunction "13_13") (pintype "input"))
      (node (ref "U8") (pin "42") (pinfunction "GPIO33_42") (pintype "unspecified"))
    )
    (net (code "63") (name "Net-(U8-GPIO34)") (class "Default")
      (node (ref "P3") (pin "14") (pinfunction "14_14") (pintype "input"))
      (node (ref "U8") (pin "43") (pinfunction "GPIO34_43") (pintype "unspecified"))
    )
    (net (code "64") (name "Net-(U8-GPIO35)") (class "Default")
      (node (ref "P3") (pin "15") (pinfunction "15_15") (pintype "input"))
      (node (ref "U8") (pin "44") (pinfunction "GPIO35_44") (pintype "unspecified"))
    )
    (net (code "65") (name "Net-(U8-GPIO36)") (class "Default")
      (node (ref "P3") (pin "16") (pinfunction "16_16") (pintype "input"))
      (node (ref "U8") (pin "45") (pinfunction "GPIO36_45") (pintype "unspecified"))
    )
    (net (code "66") (name "Net-(U8-GPIO37)") (class "Default")
      (node (ref "CN1") (pin "3") (pinfunction "3_3") (pintype "unspecified"))
      (node (ref "U8") (pin "46") (pinfunction "GPIO37_46") (pintype "unspecified"))
    )
    (net (code "67") (name "Net-(U8-GPIO38)") (class "Default")
      (node (ref "CN1") (pin "4") (pinfunction "4_4") (pintype "unspecified"))
      (node (ref "U8") (pin "47") (pinfunction "GPIO38_47") (pintype "unspecified"))
    )
    (net (code "68") (name "Net-(U8-GPIO39)") (class "Default")
      (node (ref "R16") (pin "2") (pinfunction "2_2") (pintype "input"))
      (node (ref "U8") (pin "48") (pinfunction "GPIO39_48") (pintype "unspecified"))
    )
    (net (code "69") (name "Net-(U8-GPIO40_ADC0)") (class "Default")
      (node (ref "P6") (pin "1") (pinfunction "1_1") (pintype "unspecified"))
      (node (ref "U8") (pin "49") (pinfunction "GPIO40_ADC0_49") (pintype "unspecified"))
    )
    (net (code "70") (name "Net-(U8-GPIO41_ADC1)") (class "Default")
      (node (ref "P6") (pin "2") (pinfunction "2_2") (pintype "unspecified"))
      (node (ref "U8") (pin "52") (pinfunction "GPIO41_ADC1_52") (pintype "unspecified"))
    )
    (net (code "71") (name "Net-(U8-GPIO42_ADC2)") (class "Default")
      (node (ref "P6") (pin "3") (pinfunction "3_3") (pintype "unspecified"))
      (node (ref "U8") (pin "53") (pinfunction "GPIO42_ADC2_53") (pintype "unspecified"))
    )
    (net (code "72") (name "Net-(U8-GPIO43_ADC3)") (class "Default")
      (node (ref "P6") (pin "4") (pinfunction "4_4") (pintype "unspecified"))
      (node (ref "U8") (pin "54") (pinfunction "GPIO43_ADC3_54") (pintype "unspecified"))
    )
    (net (code "73") (name "Net-(U8-GPIO44_ADC4)") (class "Default")
      (node (ref "P6") (pin "5") (pinfunction "5_5") (pintype "unspecified"))
      (node (ref "U8") (pin "55") (pinfunction "GPIO44_ADC4_55") (pintype "unspecified"))
    )
    (net (code "74") (name "Net-(U8-GPIO45_ADC5)") (class "Default")
      (node (ref "P6") (pin "6") (pinfunction "6_6") (pintype "unspecified"))
      (node (ref "U8") (pin "56") (pinfunction "GPIO45_ADC5_56") (pintype "unspecified"))
    )
    (net (code "75") (name "Net-(U8-GPIO46_ADC6)") (class "Default")
      (node (ref "P6") (pin "7") (pinfunction "7_7") (pintype "unspecified"))
      (node (ref "U8") (pin "57") (pinfunction "GPIO46_ADC6_57") (pintype "unspecified"))
    )
    (net (code "76") (name "Net-(U8-GPIO47_ADC7)") (class "Default")
      (node (ref "P6") (pin "8") (pinfunction "8_8") (pintype "unspecified"))
      (node (ref "U8") (pin "58") (pinfunction "GPIO47_ADC7_58") (pintype "unspecified"))
    )
    (net (code "77") (name "Net-(U8-SWCLK)") (class "Default")
      (node (ref "H3") (pin "1") (pinfunction "1_1") (pintype "input"))
      (node (ref "U8") (pin "33") (pinfunction "SWCLK_33") (pintype "unspecified"))
    )
    (net (code "78") (name "Net-(U8-SWDIO)") (class "Default")
      (node (ref "H3") (pin "2") (pinfunction "2_2") (pintype "input"))
      (node (ref "U8") (pin "34") (pinfunction "SWDIO_34") (pintype "unspecified"))
    )
    (net (code "79") (name "Net-(U8-USB_DM)") (class "Default")
      (node (ref "TV1") (pin "3") (pinfunction "3_3") (pintype "input"))
      (node (ref "TV1") (pin "6") (pinfunction "6_6") (pintype "input"))
      (node (ref "U8") (pin "66") (pinfunction "USB_DM_66") (pintype "unspecified"))
      (node (ref "USBC1") (pin "A7") (pinfunction "DN1_A7") (pintype "unspecified"))
      (node (ref "USBC1") (pin "B7") (pinfunction "DN2_B7") (pintype "unspecified"))
    )
    (net (code "80") (name "Net-(U8-USB_DP)") (class "Default")
      (node (ref "TV1") (pin "1") (pinfunction "1_1") (pintype "input"))
      (node (ref "TV1") (pin "4") (pinfunction "4_4") (pintype "input"))
      (node (ref "U8") (pin "67") (pinfunction "USB_DP_67") (pintype "unspecified"))
      (node (ref "USBC1") (pin "A6") (pinfunction "DP1_A6") (pintype "unspecified"))
      (node (ref "USBC1") (pin "B6") (pinfunction "DP2_B6") (pintype "unspecified"))
    )
    (net (code "81") (name "Net-(U8-VREG_FB)") (class "Default")
      (node (ref "C11") (pin "1") (pinfunction "1_1") (pintype "unspecified"))
      (node (ref "C12") (pin "1") (pinfunction "1_1") (pintype "unspecified"))
      (node (ref "C13") (pin "1") (pinfunction "1_1") (pintype "unspecified"))
      (node (ref "C8") (pin "2") (pinfunction "2_2") (pintype "input"))
      (node (ref "L3") (pin "1") (pinfunction "1_1") (pintype "unspecified"))
      (node (ref "U8") (pin "10") (pinfunction "DVDD_10") (pintype "unspecified"))
      (node (ref "U8") (pin "32") (pinfunction "DVDD_32") (pintype "unspecified"))
      (node (ref "U8") (pin "51") (pinfunction "DVDD_51") (pintype "unspecified"))
      (node (ref "U8") (pin "65") (pinfunction "VREG_FB_65") (pintype "unspecified"))
    )
    (net (code "82") (name "Net-(U8-VREG_LX)") (class "Default")
      (node (ref "L3") (pin "2") (pinfunction "2_2") (pintype "unspecified"))
      (node (ref "U8") (pin "63") (pinfunction "VREG_LX_63") (pintype "unspecified"))
    )
    (net (code "83") (name "Net-(U8-XIN)") (class "Default")
      (node (ref "U8") (pin "30") (pinfunction "XIN_30") (pintype "unspecified"))
      (node (ref "X1") (pin "1") (pinfunction "OSC1_1") (pintype "unspecified"))
    )
    (net (code "84") (name "Net-(U8-XOUT)") (class "Default")
      (node (ref "U8") (pin "31") (pinfunction "XOUT_31") (pintype "unspecified"))
      (node (ref "X1") (pin "3") (pinfunction "OSC2_3") (pintype "unspecified"))
    )
    (net (code "85") (name "unconnected-(BUZZER1-NC-Pad3)") (class "Default")
      (node (ref "BUZZER1") (pin "3") (pinfunction "NC_3") (pintype "unspecified+no_connect"))
    )
    (net (code "86") (name "unconnected-(BUZZER1-NC-Pad4)") (class "Default")
      (node (ref "BUZZER1") (pin "4") (pinfunction "NC_4") (pintype "unspecified+no_connect"))
    )
    (net (code "87") (name "unconnected-(LED2-DO-Pad1)") (class "Default")
      (node (ref "LED2") (pin "1") (pinfunction "DO_1") (pintype "unspecified+no_connect"))
    )
    (net (code "88") (name "unconnected-(RST-B-Pad2)") (class "Default")
      (node (ref "RST") (pin "2") (pinfunction "B_2") (pintype "unspecified+no_connect"))
    )
    (net (code "89") (name "unconnected-(RST-C-Pad3)") (class "Default")
      (node (ref "RST") (pin "3") (pinfunction "C_3") (pintype "unspecified+no_connect"))
    )
    (net (code "90") (name "unconnected-(TV1-Pad5)") (class "Default")
      (node (ref "TV1") (pin "5") (pinfunction "5_5") (pintype "input+no_connect"))
    )
    (net (code "91") (name "unconnected-(U1-DM-Pad5)") (class "Default")
      (node (ref "U1") (pin "5") (pinfunction "DM_5") (pintype "unspecified+no_connect"))
    )
    (net (code "92") (name "unconnected-(U1-DP-Pad4)") (class "Default")
      (node (ref "U1") (pin "4") (pinfunction "DP_4") (pintype "unspecified+no_connect"))
    )
    (net (code "93") (name "unconnected-(U2-ILIM-Pad10)") (class "Default")
      (node (ref "U2") (pin "10") (pinfunction "ILIM_10") (pintype "unspecified+no_connect"))
    )
    (net (code "94") (name "unconnected-(U2-dV{slash}dT-Pad1)") (class "Default")
      (node (ref "U2") (pin "1") (pinfunction "dV/dT_1") (pintype "unspecified+no_connect"))
    )
    (net (code "95") (name "unconnected-(U3-EN-Pad5)") (class "Default")
      (node (ref "U3") (pin "5") (pinfunction "EN_5") (pintype "unspecified+no_connect"))
    )
    (net (code "96") (name "unconnected-(U6-IO0-Pad8)") (class "Default")
      (node (ref "U6") (pin "8") (pinfunction "IO0_8") (pintype "unspecified+no_connect"))
    )
    (net (code "97") (name "unconnected-(U6-IO1-Pad9)") (class "Default")
      (node (ref "U6") (pin "9") (pinfunction "IO1_9") (pintype "unspecified+no_connect"))
    )
    (net (code "98") (name "unconnected-(U6-IO2-Pad27)") (class "Default")
      (node (ref "U6") (pin "27") (pinfunction "IO2_27") (pintype "unspecified+no_connect"))
    )
    (net (code "99") (name "unconnected-(U6-IO3-Pad26)") (class "Default")
      (node (ref "U6") (pin "26") (pinfunction "IO3_26") (pintype "unspecified+no_connect"))
    )
    (net (code "100") (name "unconnected-(U6-IO4-Pad4)") (class "Default")
      (node (ref "U6") (pin "4") (pinfunction "IO4_4") (pintype "unspecified+no_connect"))
    )
    (net (code "101") (name "unconnected-(U6-IO5-Pad5)") (class "Default")
      (node (ref "U6") (pin "5") (pinfunction "IO5_5") (pintype "unspecified+no_connect"))
    )
    (net (code "102") (name "unconnected-(U6-IO6-Pad6)") (class "Default")
      (node (ref "U6") (pin "6") (pinfunction "IO6_6") (pintype "unspecified+no_connect"))
    )
    (net (code "103") (name "unconnected-(U6-IO7-Pad7)") (class "Default")
      (node (ref "U6") (pin "7") (pinfunction "IO7_7") (pintype "unspecified+no_connect"))
    )
    (net (code "104") (name "unconnected-(U6-IO8-Pad10)") (class "Default")
      (node (ref "U6") (pin "10") (pinfunction "IO8_10") (pintype "unspecified+no_connect"))
    )
    (net (code "105") (name "unconnected-(U6-IO10-Pad11)") (class "Default")
      (node (ref "U6") (pin "11") (pinfunction "IO10_11") (pintype "unspecified+no_connect"))
    )
    (net (code "106") (name "unconnected-(U6-IO11-Pad12)") (class "Default")
      (node (ref "U6") (pin "12") (pinfunction "IO11_12") (pintype "unspecified+no_connect"))
    )
    (net (code "107") (name "unconnected-(U6-IO12-Pad13)") (class "Default")
      (node (ref "U6") (pin "13") (pinfunction "IO12_13") (pintype "unspecified+no_connect"))
    )
    (net (code "108") (name "unconnected-(U6-IO13-Pad14)") (class "Default")
      (node (ref "U6") (pin "14") (pinfunction "IO13_14") (pintype "unspecified+no_connect"))
    )
    (net (code "109") (name "unconnected-(U6-IO15-Pad23)") (class "Default")
      (node (ref "U6") (pin "23") (pinfunction "IO15_23") (pintype "unspecified+no_connect"))
    )
    (net (code "110") (name "unconnected-(U6-IO18-Pad16)") (class "Default")
      (node (ref "U6") (pin "16") (pinfunction "IO18_16") (pintype "unspecified+no_connect"))
    )
    (net (code "111") (name "unconnected-(U6-IO19-Pad17)") (class "Default")
      (node (ref "U6") (pin "17") (pinfunction "IO19_17") (pintype "unspecified+no_connect"))
    )
    (net (code "112") (name "unconnected-(U6-IO20-Pad18)") (class "Default")
      (node (ref "U6") (pin "18") (pinfunction "IO20_18") (pintype "unspecified+no_connect"))
    )
    (net (code "113") (name "unconnected-(U6-IO21-Pad19)") (class "Default")
      (node (ref "U6") (pin "19") (pinfunction "IO21_19") (pintype "unspecified+no_connect"))
    )
    (net (code "114") (name "unconnected-(U6-IO22-Pad20)") (class "Default")
      (node (ref "U6") (pin "20") (pinfunction "IO22_20") (pintype "unspecified+no_connect"))
    )
    (net (code "115") (name "unconnected-(U6-IO23-Pad21)") (class "Default")
      (node (ref "U6") (pin "21") (pinfunction "IO23_21") (pintype "unspecified+no_connect"))
    )
    (net (code "116") (name "unconnected-(U6-NC-Pad22)") (class "Default")
      (node (ref "U6") (pin "22") (pinfunction "NC_22") (pintype "unspecified+no_connect"))
    )
    (net (code "117") (name "unconnected-(USBC1-SBU1-PadA8)") (class "Default")
      (node (ref "USBC1") (pin "A8") (pinfunction "SBU1_A8") (pintype "unspecified+no_connect"))
    )
    (net (code "118") (name "unconnected-(USBC1-SBU2-PadB8)") (class "Default")
      (node (ref "USBC1") (pin "B8") (pinfunction "SBU2_B8") (pintype "unspecified+no_connect"))
    )
    (net (code "119") (name "unconnected-(USR-FLASH-B-Pad2)") (class "Default")
      (node (ref "USR-FLASH") (pin "2") (pinfunction "B_2") (pintype "unspecified+no_connect"))
    )
    (net (code "120") (name "unconnected-(USR-FLASH-C-Pad3)") (class "Default")
      (node (ref "USR-FLASH") (pin "3") (pinfunction "C_3") (pintype "unspecified+no_connect"))
    )
  )
)
